# PCB-DISPARRAY4c.net
KiCad netlist of a schematic drawn in EAGLE
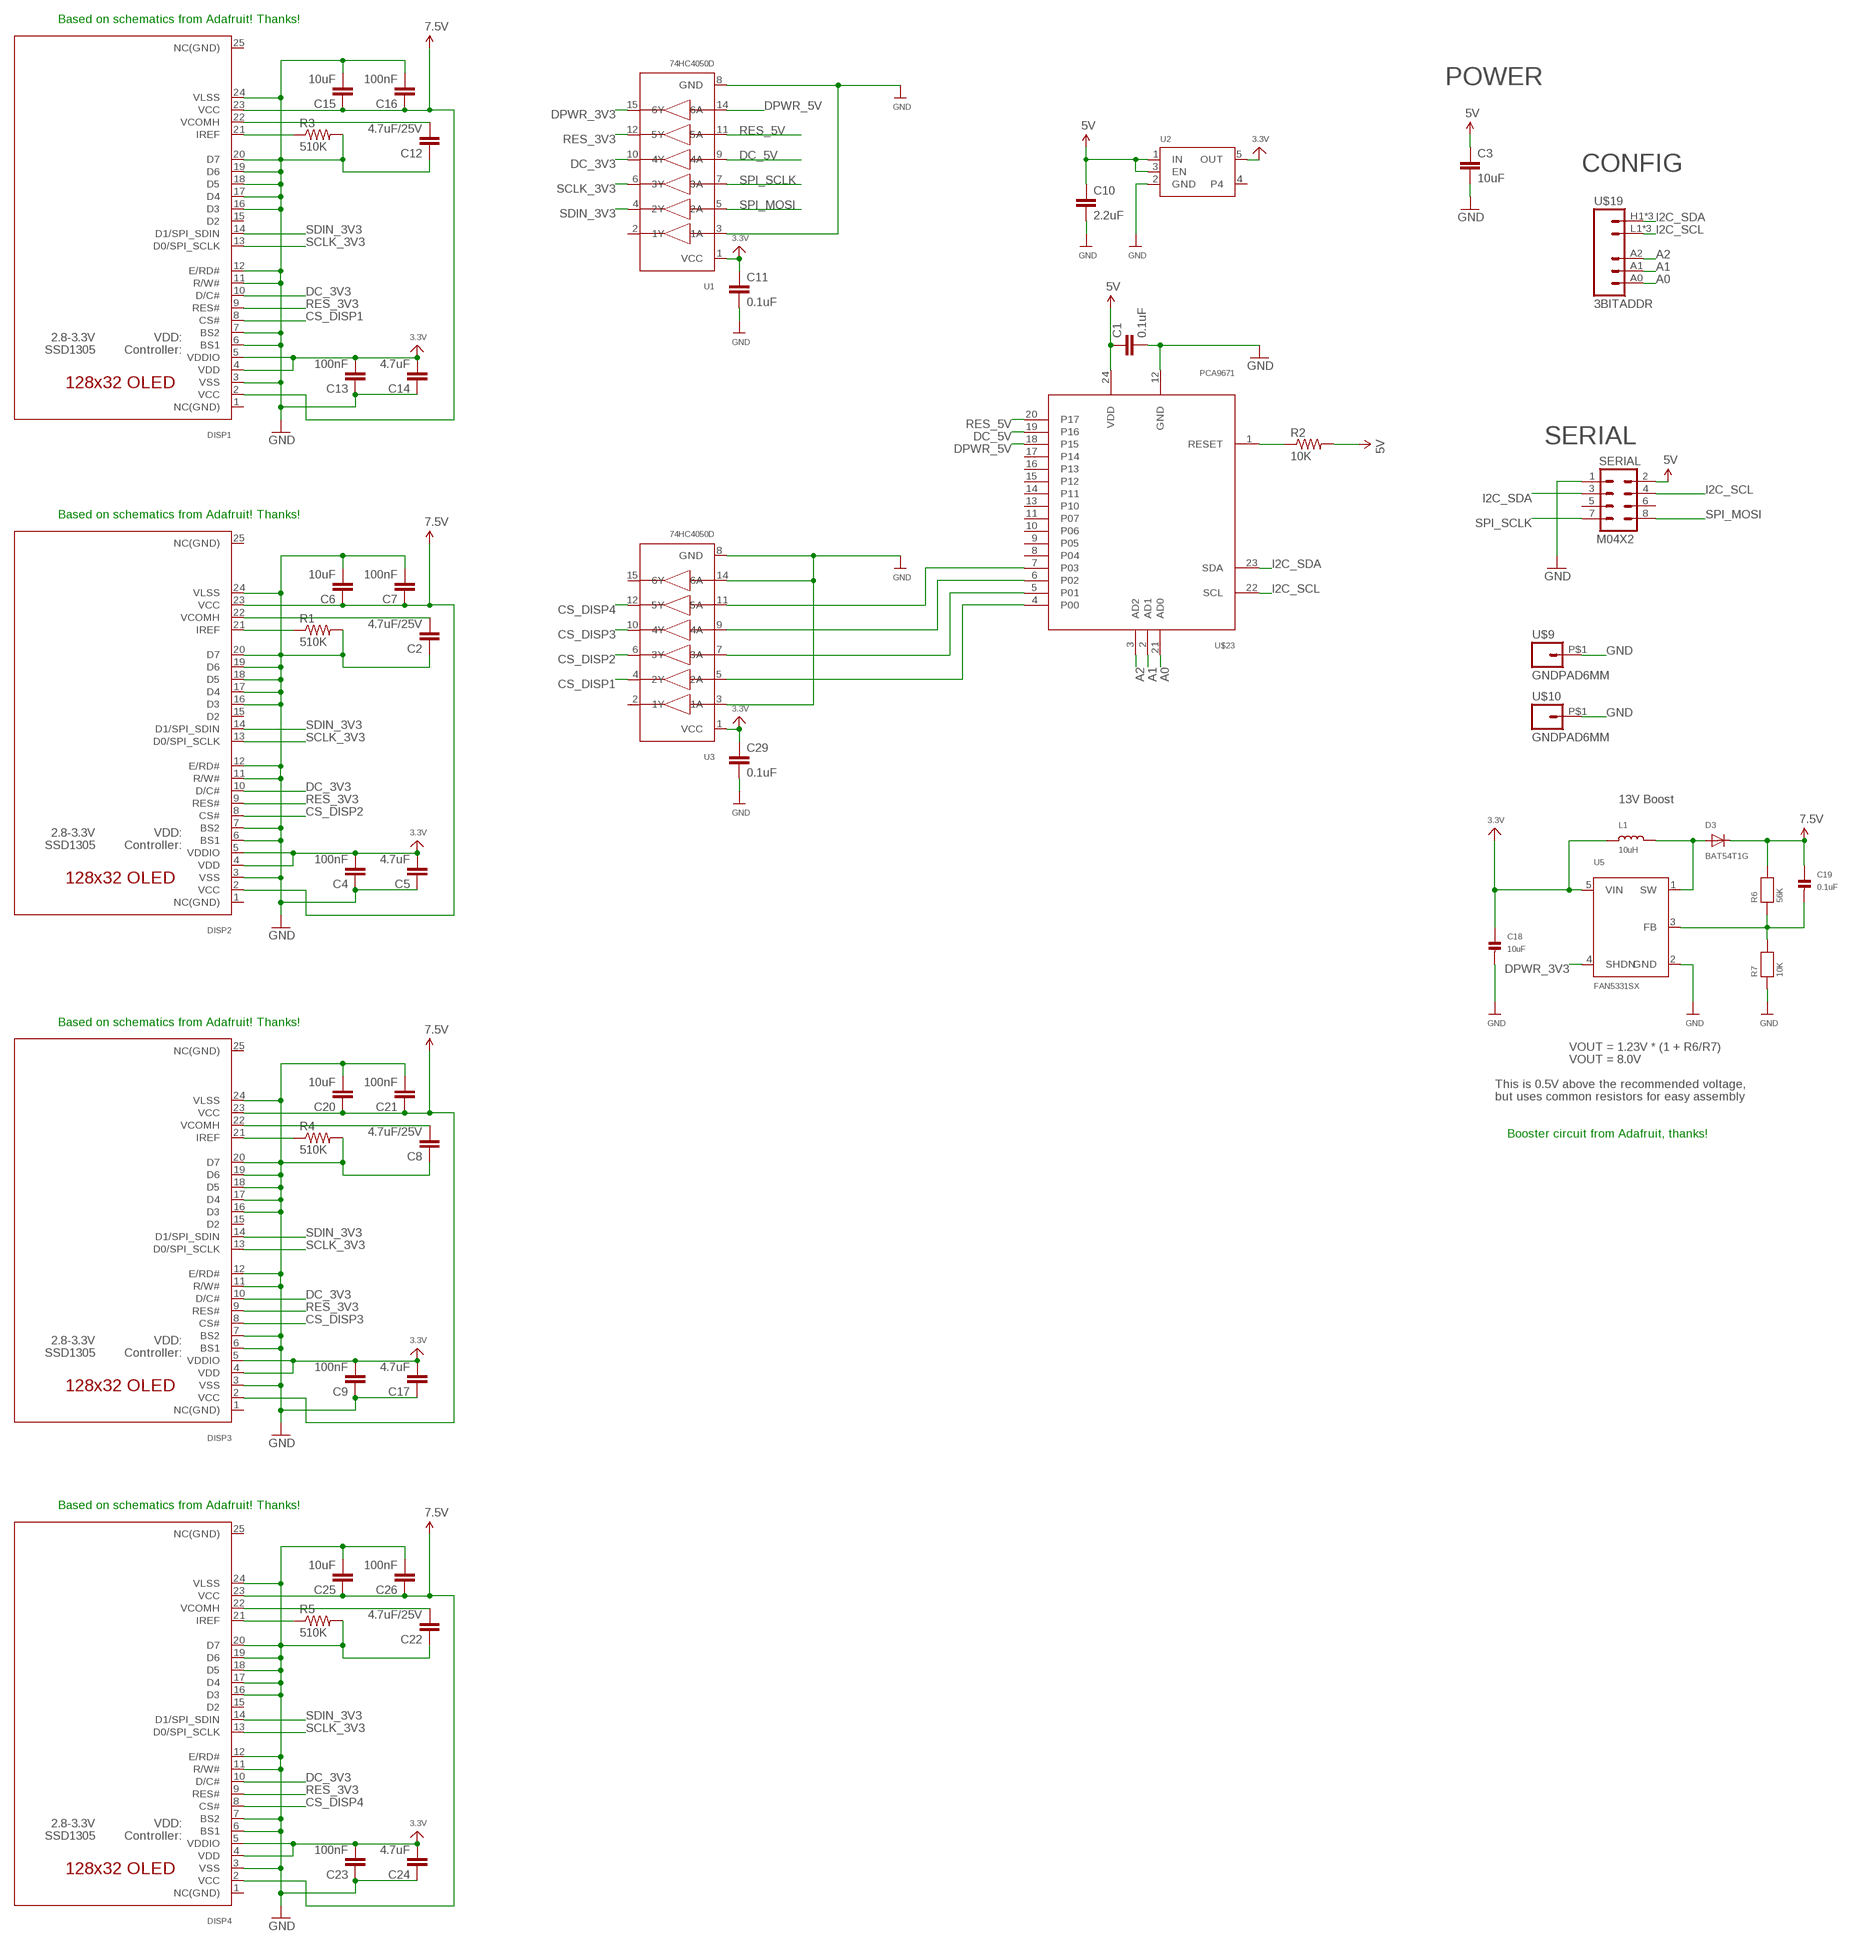
[diagram p0: schematic, sheet 1]

(export (version "E")
  (design (tool "Eeschema 10.0.6"))
  (components
    (comp (ref "C1")
      (value "0.1uF")
      (footprint "eagle-import:0603-CAP")
      (libsource (lib "eagle-import") (part "CAP0603-CAP"))
    )
    (comp (ref "C2")
      (value "4.7uF/25V")
      (footprint "eagle-import:0805")
      (libsource (lib "eagle-import") (part "CAP0805"))
    )
    (comp (ref "C3")
      (value "10uF")
      (footprint "eagle-import:0805")
      (libsource (lib "eagle-import") (part "CAP0805"))
    )
    (comp (ref "C4")
      (value "100nF")
      (footprint "eagle-import:0603-CAP")
      (libsource (lib "eagle-import") (part "CAP0603-CAP"))
    )
    (comp (ref "C5")
      (value "4.7uF")
      (footprint "eagle-import:0603-CAP")
      (libsource (lib "eagle-import") (part "CAP0603-CAP"))
    )
    (comp (ref "C6")
      (value "10uF")
      (footprint "eagle-import:0805")
      (libsource (lib "eagle-import") (part "CAP0805"))
    )
    (comp (ref "C7")
      (value "100nF")
      (footprint "eagle-import:0805")
      (libsource (lib "eagle-import") (part "CAP0805"))
    )
    (comp (ref "C8")
      (value "4.7uF/25V")
      (footprint "eagle-import:0805")
      (libsource (lib "eagle-import") (part "CAP0805"))
    )
    (comp (ref "C9")
      (value "100nF")
      (footprint "eagle-import:0603-CAP")
      (libsource (lib "eagle-import") (part "CAP0603-CAP"))
    )
    (comp (ref "C10")
      (value "2.2uF")
      (footprint "eagle-import:0603-CAP")
      (libsource (lib "eagle-import") (part "CAP0603-CAP"))
    )
    (comp (ref "C11")
      (value "0.1uF")
      (footprint "eagle-import:0603-CAP")
      (libsource (lib "eagle-import") (part "CAP0603-CAP"))
    )
    (comp (ref "C12")
      (value "4.7uF/25V")
      (footprint "eagle-import:0805")
      (libsource (lib "eagle-import") (part "CAP0805"))
    )
    (comp (ref "C13")
      (value "100nF")
      (footprint "eagle-import:0603-CAP")
      (libsource (lib "eagle-import") (part "CAP0603-CAP"))
    )
    (comp (ref "C14")
      (value "4.7uF")
      (footprint "eagle-import:0603-CAP")
      (libsource (lib "eagle-import") (part "CAP0603-CAP"))
    )
    (comp (ref "C15")
      (value "10uF")
      (footprint "eagle-import:0805")
      (libsource (lib "eagle-import") (part "CAP0805"))
    )
    (comp (ref "C16")
      (value "100nF")
      (footprint "eagle-import:0603-CAP")
      (libsource (lib "eagle-import") (part "CAP0603-CAP"))
    )
    (comp (ref "C17")
      (value "4.7uF")
      (footprint "eagle-import:0603-CAP")
      (libsource (lib "eagle-import") (part "CAP0603-CAP"))
    )
    (comp (ref "C18")
      (value "10uF")
      (footprint "eagle-import:0805")
      (libsource (lib "eagle-import") (part "CAP_CERAMIC0805"))
    )
    (comp (ref "C19")
      (value "0.1uF")
      (footprint "eagle-import:0603")
      (libsource (lib "eagle-import") (part "CAP_CERAMIC0603"))
    )
    (comp (ref "C20")
      (value "10uF")
      (footprint "eagle-import:0805")
      (libsource (lib "eagle-import") (part "CAP0805"))
    )
    (comp (ref "C21")
      (value "100nF")
      (footprint "eagle-import:0603-CAP")
      (libsource (lib "eagle-import") (part "CAP0603-CAP"))
    )
    (comp (ref "C22")
      (value "4.7uF/25V")
      (footprint "eagle-import:0805")
      (libsource (lib "eagle-import") (part "CAP0805"))
    )
    (comp (ref "C23")
      (value "100nF")
      (footprint "eagle-import:0603-CAP")
      (libsource (lib "eagle-import") (part "CAP0603-CAP"))
    )
    (comp (ref "C24")
      (value "4.7uF")
      (footprint "eagle-import:0603-CAP")
      (libsource (lib "eagle-import") (part "CAP0603-CAP"))
    )
    (comp (ref "C25")
      (value "10uF")
      (footprint "eagle-import:0805")
      (libsource (lib "eagle-import") (part "CAP0805"))
    )
    (comp (ref "C26")
      (value "100nF")
      (footprint "eagle-import:0603-CAP")
      (libsource (lib "eagle-import") (part "CAP0603-CAP"))
    )
    (comp (ref "C29")
      (value "0.1uF")
      (footprint "eagle-import:0603-CAP")
      (libsource (lib "eagle-import") (part "CAP0603-CAP"))
    )
    (comp (ref "D3")
      (value "BAT54T1G")
      (footprint "eagle-import:SOD-123")
      (libsource (lib "eagle-import") (part "DIODESOD-123"))
    )
    (comp (ref "DISP1")
      (value "ER-OLED0.91-2TOP")
      (footprint "eagle-import:ER_OLED0.91-2")
      (libsource (lib "eagle-import") (part "ER-OLED0.91-2TOP"))
    )
    (comp (ref "DISP2")
      (value "ER-OLED0.91-2TOP")
      (footprint "eagle-import:ER_OLED0.91-2")
      (libsource (lib "eagle-import") (part "ER-OLED0.91-2TOP"))
    )
    (comp (ref "DISP3")
      (value "ER-OLED0.91-2TOP")
      (footprint "eagle-import:ER_OLED0.91-2")
      (libsource (lib "eagle-import") (part "ER-OLED0.91-2TOP"))
    )
    (comp (ref "DISP4")
      (value "ER-OLED0.91-2TOP")
      (footprint "eagle-import:ER_OLED0.91-2")
      (libsource (lib "eagle-import") (part "ER-OLED0.91-2TOP"))
    )
    (comp (ref "L1")
      (value "10uH")
      (footprint "eagle-import:INDUCTOR_1007")
      (libsource (lib "eagle-import") (part "INDUCTOR"))
    )
    (comp (ref "R1")
      (value "510K")
      (footprint "eagle-import:0603-RES")
      (libsource (lib "eagle-import") (part "RESISTOR0603-RES"))
    )
    (comp (ref "R2")
      (value "10K")
      (footprint "eagle-import:0603-RES")
      (libsource (lib "eagle-import") (part "RESISTOR0603-RES"))
    )
    (comp (ref "R3")
      (value "510K")
      (footprint "eagle-import:0603-RES")
      (libsource (lib "eagle-import") (part "RESISTOR0603-RES"))
    )
    (comp (ref "R4")
      (value "510K")
      (footprint "eagle-import:0603-RES")
      (libsource (lib "eagle-import") (part "RESISTOR0603-RES"))
    )
    (comp (ref "R5")
      (value "510K")
      (footprint "eagle-import:0603-RES")
      (libsource (lib "eagle-import") (part "RESISTOR0603-RES"))
    )
    (comp (ref "R6")
      (value "56K")
      (footprint "eagle-import:0603")
      (libsource (lib "eagle-import") (part "RESISTOR0603"))
    )
    (comp (ref "R7")
      (value "10K")
      (footprint "eagle-import:0603")
      (libsource (lib "eagle-import") (part "RESISTOR0603"))
    )
    (comp (ref "SERIAL")
      (value "M04X2")
      (footprint "eagle-import:2X4")
      (libsource (lib "eagle-import") (part "M04X2"))
    )
    (comp (ref "U$9")
      (value "GNDPAD6MM")
      (footprint "eagle-import:3.2MMPAD6MM")
      (libsource (lib "eagle-import") (part "GNDPAD6MM"))
    )
    (comp (ref "U$10")
      (value "GNDPAD6MM")
      (footprint "eagle-import:3.2MMPAD6MM")
      (libsource (lib "eagle-import") (part "GNDPAD6MM"))
    )
    (comp (ref "U$19")
      (value "3BITADDR")
      (footprint "eagle-import:3BITADDR")
      (libsource (lib "eagle-import") (part "3BITADDR"))
    )
    (comp (ref "U$23")
      (value "PCA9671")
      (footprint "eagle-import:TSSOP24")
      (libsource (lib "eagle-import") (part "PCA9671"))
    )
    (comp (ref "U1")
      (value "74HC4050D")
      (footprint "eagle-import:TSSOP16")
      (libsource (lib "eagle-import") (part "74HC4050DTSSOP16"))
    )
    (comp (ref "U2")
      (value "VREG_SOT23-5")
      (footprint "eagle-import:SOT23-5")
      (libsource (lib "eagle-import") (part "VREG_SOT23-5"))
    )
    (comp (ref "U3")
      (value "74HC4050D")
      (footprint "eagle-import:TSSOP16")
      (libsource (lib "eagle-import") (part "74HC4050DTSSOP16"))
    )
    (comp (ref "U5")
      (value "FAN5331SX")
      (footprint "eagle-import:SOT23-5")
      (libsource (lib "eagle-import") (part "FAN5331"))
    )
  )
  (nets
    (net (code "1") (name "3.3V") (class "Default")
      (node (ref "C11") (pin "1") (pinfunction "1_1") (pintype "passive"))
      (node (ref "C13") (pin "2") (pinfunction "2_2") (pintype "passive"))
      (node (ref "C14") (pin "2") (pinfunction "2_2") (pintype "passive"))
      (node (ref "C17") (pin "2") (pinfunction "2_2") (pintype "passive"))
      (node (ref "C18") (pin "1") (pinfunction "P$1_1") (pintype "passive"))
      (node (ref "C23") (pin "2") (pinfunction "2_2") (pintype "passive"))
      (node (ref "C24") (pin "2") (pinfunction "2_2") (pintype "passive"))
      (node (ref "C29") (pin "1") (pinfunction "1_1") (pintype "passive"))
      (node (ref "C4") (pin "2") (pinfunction "2_2") (pintype "passive"))
      (node (ref "C5") (pin "2") (pinfunction "2_2") (pintype "passive"))
      (node (ref "C9") (pin "2") (pinfunction "2_2") (pintype "passive"))
      (node (ref "DISP1") (pin "4") (pinfunction "VDD_4") (pintype "power_in"))
      (node (ref "DISP1") (pin "5") (pinfunction "VDDIO_5") (pintype "power_in"))
      (node (ref "DISP2") (pin "4") (pinfunction "VDD_4") (pintype "power_in"))
      (node (ref "DISP2") (pin "5") (pinfunction "VDDIO_5") (pintype "power_in"))
      (node (ref "DISP3") (pin "4") (pinfunction "VDD_4") (pintype "power_in"))
      (node (ref "DISP3") (pin "5") (pinfunction "VDDIO_5") (pintype "power_in"))
      (node (ref "DISP4") (pin "4") (pinfunction "VDD_4") (pintype "power_in"))
      (node (ref "DISP4") (pin "5") (pinfunction "VDDIO_5") (pintype "power_in"))
      (node (ref "L1") (pin "P$1") (pinfunction "1_P$1") (pintype "passive"))
      (node (ref "U1") (pin "1") (pinfunction "VCC_1") (pintype "bidirectional"))
      (node (ref "U2") (pin "5") (pinfunction "OUT_5") (pintype "bidirectional"))
      (node (ref "U3") (pin "1") (pinfunction "VCC_1") (pintype "bidirectional"))
      (node (ref "U5") (pin "5") (pinfunction "VIN_5") (pintype "bidirectional"))
    )
    (net (code "2") (name "5V") (class "Default")
      (node (ref "C1") (pin "1") (pinfunction "1_1") (pintype "passive"))
      (node (ref "C10") (pin "1") (pinfunction "1_1") (pintype "passive"))
      (node (ref "C3") (pin "1") (pinfunction "1_1") (pintype "passive"))
      (node (ref "R2") (pin "2") (pinfunction "2_2") (pintype "passive"))
      (node (ref "SERIAL") (pin "2") (pinfunction "2_2") (pintype "passive"))
      (node (ref "U$23") (pin "24") (pinfunction "VDD_24") (pintype "power_in"))
      (node (ref "U2") (pin "1") (pinfunction "IN_1") (pintype "bidirectional"))
      (node (ref "U2") (pin "3") (pinfunction "EN_3") (pintype "bidirectional"))
    )
    (net (code "3") (name "7.5V") (class "Default")
      (node (ref "C15") (pin "1") (pinfunction "1_1") (pintype "passive"))
      (node (ref "C16") (pin "1") (pinfunction "1_1") (pintype "passive"))
      (node (ref "C19") (pin "1") (pinfunction "P$1_1") (pintype "passive"))
      (node (ref "C20") (pin "1") (pinfunction "1_1") (pintype "passive"))
      (node (ref "C21") (pin "1") (pinfunction "1_1") (pintype "passive"))
      (node (ref "C25") (pin "1") (pinfunction "1_1") (pintype "passive"))
      (node (ref "C26") (pin "1") (pinfunction "1_1") (pintype "passive"))
      (node (ref "C6") (pin "1") (pinfunction "1_1") (pintype "passive"))
      (node (ref "C7") (pin "1") (pinfunction "1_1") (pintype "passive"))
      (node (ref "D3") (pin "C") (pinfunction "C_C") (pintype "passive"))
      (node (ref "DISP1") (pin "2") (pinfunction "VCC_2") (pintype "power_in"))
      (node (ref "DISP1") (pin "23") (pinfunction "VCC_23") (pintype "power_in"))
      (node (ref "DISP2") (pin "2") (pinfunction "VCC_2") (pintype "power_in"))
      (node (ref "DISP2") (pin "23") (pinfunction "VCC_23") (pintype "power_in"))
      (node (ref "DISP3") (pin "2") (pinfunction "VCC_2") (pintype "power_in"))
      (node (ref "DISP3") (pin "23") (pinfunction "VCC_23") (pintype "power_in"))
      (node (ref "DISP4") (pin "2") (pinfunction "VCC_2") (pintype "power_in"))
      (node (ref "DISP4") (pin "23") (pinfunction "VCC_23") (pintype "power_in"))
      (node (ref "R6") (pin "2") (pinfunction "2_2") (pintype "passive"))
    )
    (net (code "4") (name "A0") (class "Default")
      (node (ref "U$19") (pin "A0") (pinfunction "A0_A0") (pintype "passive"))
      (node (ref "U$23") (pin "21") (pinfunction "AD0_21") (pintype "input"))
    )
    (net (code "5") (name "A1") (class "Default")
      (node (ref "U$19") (pin "A1") (pinfunction "A1_A1") (pintype "passive"))
      (node (ref "U$23") (pin "2") (pinfunction "AD1_2") (pintype "input"))
    )
    (net (code "6") (name "A2") (class "Default")
      (node (ref "U$19") (pin "A2") (pinfunction "A2_A2") (pintype "passive"))
      (node (ref "U$23") (pin "3") (pinfunction "AD2_3") (pintype "input"))
    )
    (net (code "7") (name "CS_DISP1") (class "Default")
      (node (ref "DISP1") (pin "8") (pinfunction "CS#_8") (pintype "input"))
      (node (ref "U3") (pin "4") (pinfunction "2Y_4") (pintype "bidirectional"))
    )
    (net (code "8") (name "CS_DISP2") (class "Default")
      (node (ref "DISP2") (pin "8") (pinfunction "CS#_8") (pintype "input"))
      (node (ref "U3") (pin "6") (pinfunction "3Y_6") (pintype "bidirectional"))
    )
    (net (code "9") (name "CS_DISP3") (class "Default")
      (node (ref "DISP3") (pin "8") (pinfunction "CS#_8") (pintype "input"))
      (node (ref "U3") (pin "10") (pinfunction "4Y_10") (pintype "bidirectional"))
    )
    (net (code "10") (name "CS_DISP4") (class "Default")
      (node (ref "DISP4") (pin "8") (pinfunction "CS#_8") (pintype "input"))
      (node (ref "U3") (pin "12") (pinfunction "5Y_12") (pintype "bidirectional"))
    )
    (net (code "11") (name "DC_3V3") (class "Default")
      (node (ref "DISP1") (pin "10") (pinfunction "D/C#_10") (pintype "input"))
      (node (ref "DISP2") (pin "10") (pinfunction "D/C#_10") (pintype "input"))
      (node (ref "DISP3") (pin "10") (pinfunction "D/C#_10") (pintype "input"))
      (node (ref "DISP4") (pin "10") (pinfunction "D/C#_10") (pintype "input"))
      (node (ref "U1") (pin "10") (pinfunction "4Y_10") (pintype "bidirectional"))
    )
    (net (code "12") (name "DC_5V") (class "Default")
      (node (ref "U$23") (pin "19") (pinfunction "P16_19") (pintype "output"))
      (node (ref "U1") (pin "9") (pinfunction "4A_9") (pintype "bidirectional"))
    )
    (net (code "13") (name "DPWR_3V3") (class "Default")
      (node (ref "U1") (pin "15") (pinfunction "6Y_15") (pintype "bidirectional"))
      (node (ref "U5") (pin "4") (pinfunction "SHDN_4") (pintype "bidirectional"))
    )
    (net (code "14") (name "DPWR_5V") (class "Default")
      (node (ref "U$23") (pin "18") (pinfunction "P15_18") (pintype "output"))
      (node (ref "U1") (pin "14") (pinfunction "6A_14") (pintype "bidirectional"))
    )
    (net (code "15") (name "GND") (class "Default")
      (node (ref "C1") (pin "2") (pinfunction "2_2") (pintype "passive"))
      (node (ref "C10") (pin "2") (pinfunction "2_2") (pintype "passive"))
      (node (ref "C11") (pin "2") (pinfunction "2_2") (pintype "passive"))
      (node (ref "C12") (pin "1") (pinfunction "1_1") (pintype "passive"))
      (node (ref "C13") (pin "1") (pinfunction "1_1") (pintype "passive"))
      (node (ref "C14") (pin "1") (pinfunction "1_1") (pintype "passive"))
      (node (ref "C15") (pin "2") (pinfunction "2_2") (pintype "passive"))
      (node (ref "C16") (pin "2") (pinfunction "2_2") (pintype "passive"))
      (node (ref "C17") (pin "1") (pinfunction "1_1") (pintype "passive"))
      (node (ref "C18") (pin "2") (pinfunction "P$2_2") (pintype "passive"))
      (node (ref "C2") (pin "1") (pinfunction "1_1") (pintype "passive"))
      (node (ref "C20") (pin "2") (pinfunction "2_2") (pintype "passive"))
      (node (ref "C21") (pin "2") (pinfunction "2_2") (pintype "passive"))
      (node (ref "C22") (pin "1") (pinfunction "1_1") (pintype "passive"))
      (node (ref "C23") (pin "1") (pinfunction "1_1") (pintype "passive"))
      (node (ref "C24") (pin "1") (pinfunction "1_1") (pintype "passive"))
      (node (ref "C25") (pin "2") (pinfunction "2_2") (pintype "passive"))
      (node (ref "C26") (pin "2") (pinfunction "2_2") (pintype "passive"))
      (node (ref "C29") (pin "2") (pinfunction "2_2") (pintype "passive"))
      (node (ref "C3") (pin "2") (pinfunction "2_2") (pintype "passive"))
      (node (ref "C4") (pin "1") (pinfunction "1_1") (pintype "passive"))
      (node (ref "C5") (pin "1") (pinfunction "1_1") (pintype "passive"))
      (node (ref "C6") (pin "2") (pinfunction "2_2") (pintype "passive"))
      (node (ref "C7") (pin "2") (pinfunction "2_2") (pintype "passive"))
      (node (ref "C8") (pin "1") (pinfunction "1_1") (pintype "passive"))
      (node (ref "C9") (pin "1") (pinfunction "1_1") (pintype "passive"))
      (node (ref "DISP1") (pin "11") (pinfunction "R/W#_11") (pintype "input"))
      (node (ref "DISP1") (pin "12") (pinfunction "E/RD#_12") (pintype "input"))
      (node (ref "DISP1") (pin "16") (pinfunction "D3_16") (pintype "bidirectional"))
      (node (ref "DISP1") (pin "17") (pinfunction "D4_17") (pintype "bidirectional"))
      (node (ref "DISP1") (pin "18") (pinfunction "D5_18") (pintype "bidirectional"))
      (node (ref "DISP1") (pin "19") (pinfunction "D6_19") (pintype "bidirectional"))
      (node (ref "DISP1") (pin "20") (pinfunction "D7_20") (pintype "bidirectional"))
      (node (ref "DISP1") (pin "24") (pinfunction "VLSS_24") (pintype "power_in"))
      (node (ref "DISP1") (pin "3") (pinfunction "VSS_3") (pintype "power_in"))
      (node (ref "DISP1") (pin "6") (pinfunction "BS1_6") (pintype "input"))
      (node (ref "DISP1") (pin "7") (pinfunction "BS2_7") (pintype "input"))
      (node (ref "DISP2") (pin "11") (pinfunction "R/W#_11") (pintype "input"))
      (node (ref "DISP2") (pin "12") (pinfunction "E/RD#_12") (pintype "input"))
      (node (ref "DISP2") (pin "16") (pinfunction "D3_16") (pintype "bidirectional"))
      (node (ref "DISP2") (pin "17") (pinfunction "D4_17") (pintype "bidirectional"))
      (node (ref "DISP2") (pin "18") (pinfunction "D5_18") (pintype "bidirectional"))
      (node (ref "DISP2") (pin "19") (pinfunction "D6_19") (pintype "bidirectional"))
      (node (ref "DISP2") (pin "20") (pinfunction "D7_20") (pintype "bidirectional"))
      (node (ref "DISP2") (pin "24") (pinfunction "VLSS_24") (pintype "power_in"))
      (node (ref "DISP2") (pin "3") (pinfunction "VSS_3") (pintype "power_in"))
      (node (ref "DISP2") (pin "6") (pinfunction "BS1_6") (pintype "input"))
      (node (ref "DISP2") (pin "7") (pinfunction "BS2_7") (pintype "input"))
      (node (ref "DISP3") (pin "11") (pinfunction "R/W#_11") (pintype "input"))
      (node (ref "DISP3") (pin "12") (pinfunction "E/RD#_12") (pintype "input"))
      (node (ref "DISP3") (pin "16") (pinfunction "D3_16") (pintype "bidirectional"))
      (node (ref "DISP3") (pin "17") (pinfunction "D4_17") (pintype "bidirectional"))
      (node (ref "DISP3") (pin "18") (pinfunction "D5_18") (pintype "bidirectional"))
      (node (ref "DISP3") (pin "19") (pinfunction "D6_19") (pintype "bidirectional"))
      (node (ref "DISP3") (pin "20") (pinfunction "D7_20") (pintype "bidirectional"))
      (node (ref "DISP3") (pin "24") (pinfunction "VLSS_24") (pintype "power_in"))
      (node (ref "DISP3") (pin "3") (pinfunction "VSS_3") (pintype "power_in"))
      (node (ref "DISP3") (pin "6") (pinfunction "BS1_6") (pintype "input"))
      (node (ref "DISP3") (pin "7") (pinfunction "BS2_7") (pintype "input"))
      (node (ref "DISP4") (pin "11") (pinfunction "R/W#_11") (pintype "input"))
      (node (ref "DISP4") (pin "12") (pinfunction "E/RD#_12") (pintype "input"))
      (node (ref "DISP4") (pin "16") (pinfunction "D3_16") (pintype "bidirectional"))
      (node (ref "DISP4") (pin "17") (pinfunction "D4_17") (pintype "bidirectional"))
      (node (ref "DISP4") (pin "18") (pinfunction "D5_18") (pintype "bidirectional"))
      (node (ref "DISP4") (pin "19") (pinfunction "D6_19") (pintype "bidirectional"))
      (node (ref "DISP4") (pin "20") (pinfunction "D7_20") (pintype "bidirectional"))
      (node (ref "DISP4") (pin "24") (pinfunction "VLSS_24") (pintype "power_in"))
      (node (ref "DISP4") (pin "3") (pinfunction "VSS_3") (pintype "power_in"))
      (node (ref "DISP4") (pin "6") (pinfunction "BS1_6") (pintype "input"))
      (node (ref "DISP4") (pin "7") (pinfunction "BS2_7") (pintype "input"))
      (node (ref "R1") (pin "2") (pinfunction "2_2") (pintype "passive"))
      (node (ref "R3") (pin "2") (pinfunction "2_2") (pintype "passive"))
      (node (ref "R4") (pin "2") (pinfunction "2_2") (pintype "passive"))
      (node (ref "R5") (pin "2") (pinfunction "2_2") (pintype "passive"))
      (node (ref "R7") (pin "1") (pinfunction "1_1") (pintype "passive"))
      (node (ref "SERIAL") (pin "1") (pinfunction "1_1") (pintype "passive"))
      (node (ref "U$10") (pin "P$1") (pinfunction "1_P$1") (pintype "passive"))
      (node (ref "U$23") (pin "12") (pinfunction "GND_12") (pintype "power_in"))
      (node (ref "U$9") (pin "P$1") (pinfunction "1_P$1") (pintype "passive"))
      (node (ref "U1") (pin "3") (pinfunction "1A_3") (pintype "bidirectional"))
      (node (ref "U1") (pin "8") (pinfunction "GND_8") (pintype "bidirectional"))
      (node (ref "U2") (pin "2") (pinfunction "GND_2") (pintype "bidirectional"))
      (node (ref "U3") (pin "14") (pinfunction "6A_14") (pintype "bidirectional"))
      (node (ref "U3") (pin "3") (pinfunction "1A_3") (pintype "bidirectional"))
      (node (ref "U3") (pin "8") (pinfunction "GND_8") (pintype "bidirectional"))
      (node (ref "U5") (pin "2") (pinfunction "GND_2") (pintype "bidirectional"))
    )
    (net (code "16") (name "I2C_SCL") (class "Default")
      (node (ref "SERIAL") (pin "4") (pinfunction "4_4") (pintype "passive"))
      (node (ref "U$19") (pin "L1") (pinfunction "GND_L1") (pintype "passive"))
      (node (ref "U$19") (pin "L2") (pinfunction "GND_L2") (pintype "passive"))
      (node (ref "U$19") (pin "L3") (pinfunction "GND_L3") (pintype "passive"))
      (node (ref "U$23") (pin "22") (pinfunction "SCL_22") (pintype "input"))
    )
    (net (code "17") (name "I2C_SDA") (class "Default")
      (node (ref "SERIAL") (pin "3") (pinfunction "3_3") (pintype "passive"))
      (node (ref "U$19") (pin "H1") (pinfunction "VCC_H1") (pintype "passive"))
      (node (ref "U$19") (pin "H2") (pinfunction "VCC_H2") (pintype "passive"))
      (node (ref "U$19") (pin "H3") (pinfunction "VCC_H3") (pintype "passive"))
      (node (ref "U$23") (pin "23") (pinfunction "SDA_23") (pintype "input"))
    )
    (net (code "18") (name "Net-(C19-P$2)") (class "Default")
      (node (ref "C19") (pin "2") (pinfunction "P$2_2") (pintype "passive"))
      (node (ref "R6") (pin "1") (pinfunction "1_1") (pintype "passive"))
      (node (ref "R7") (pin "2") (pinfunction "2_2") (pintype "passive"))
      (node (ref "U5") (pin "3") (pinfunction "FB_3") (pintype "bidirectional"))
    )
    (net (code "19") (name "Net-(DISP1-IREF)") (class "Default")
      (node (ref "DISP1") (pin "21") (pinfunction "IREF_21") (pintype "input"))
      (node (ref "R3") (pin "1") (pinfunction "1_1") (pintype "passive"))
    )
    (net (code "20") (name "Net-(DISP1-VCOMH)") (class "Default")
      (node (ref "C12") (pin "2") (pinfunction "2_2") (pintype "passive"))
      (node (ref "DISP1") (pin "22") (pinfunction "VCOMH_22") (pintype "output"))
    )
    (net (code "21") (name "Net-(DISP2-IREF)") (class "Default")
      (node (ref "DISP2") (pin "21") (pinfunction "IREF_21") (pintype "input"))
      (node (ref "R1") (pin "1") (pinfunction "1_1") (pintype "passive"))
    )
    (net (code "22") (name "Net-(DISP2-VCOMH)") (class "Default")
      (node (ref "C2") (pin "2") (pinfunction "2_2") (pintype "passive"))
      (node (ref "DISP2") (pin "22") (pinfunction "VCOMH_22") (pintype "output"))
    )
    (net (code "23") (name "Net-(DISP3-IREF)") (class "Default")
      (node (ref "DISP3") (pin "21") (pinfunction "IREF_21") (pintype "input"))
      (node (ref "R4") (pin "1") (pinfunction "1_1") (pintype "passive"))
    )
    (net (code "24") (name "Net-(DISP3-VCOMH)") (class "Default")
      (node (ref "C8") (pin "2") (pinfunction "2_2") (pintype "passive"))
      (node (ref "DISP3") (pin "22") (pinfunction "VCOMH_22") (pintype "output"))
    )
    (net (code "25") (name "Net-(DISP4-IREF)") (class "Default")
      (node (ref "DISP4") (pin "21") (pinfunction "IREF_21") (pintype "input"))
      (node (ref "R5") (pin "1") (pinfunction "1_1") (pintype "passive"))
    )
    (net (code "26") (name "Net-(DISP4-VCOMH)") (class "Default")
      (node (ref "C22") (pin "2") (pinfunction "2_2") (pintype "passive"))
      (node (ref "DISP4") (pin "22") (pinfunction "VCOMH_22") (pintype "output"))
    )
    (net (code "27") (name "Net-(L1-2)") (class "Default")
      (node (ref "D3") (pin "A") (pinfunction "A_A") (pintype "passive"))
      (node (ref "L1") (pin "P$2") (pinfunction "2_P$2") (pintype "passive"))
      (node (ref "U5") (pin "1") (pinfunction "SW_1") (pintype "bidirectional"))
    )
    (net (code "28") (name "Net-(U$23-P00)") (class "Default")
      (node (ref "U$23") (pin "4") (pinfunction "P00_4") (pintype "output"))
      (node (ref "U3") (pin "5") (pinfunction "2A_5") (pintype "bidirectional"))
    )
    (net (code "29") (name "Net-(U$23-P01)") (class "Default")
      (node (ref "U$23") (pin "5") (pinfunction "P01_5") (pintype "output"))
      (node (ref "U3") (pin "7") (pinfunction "3A_7") (pintype "bidirectional"))
    )
    (net (code "30") (name "Net-(U$23-P02)") (class "Default")
      (node (ref "U$23") (pin "6") (pinfunction "P02_6") (pintype "output"))
      (node (ref "U3") (pin "9") (pinfunction "4A_9") (pintype "bidirectional"))
    )
    (net (code "31") (name "Net-(U$23-P03)") (class "Default")
      (node (ref "U$23") (pin "7") (pinfunction "P03_7") (pintype "output"))
      (node (ref "U3") (pin "11") (pinfunction "5A_11") (pintype "bidirectional"))
    )
    (net (code "32") (name "Net-(U$23-RESET)") (class "Default")
      (node (ref "R2") (pin "1") (pinfunction "1_1") (pintype "passive"))
      (node (ref "U$23") (pin "1") (pinfunction "RESET_1") (pintype "input"))
    )
    (net (code "33") (name "RES_3V3") (class "Default")
      (node (ref "DISP1") (pin "9") (pinfunction "RES#_9") (pintype "input"))
      (node (ref "DISP2") (pin "9") (pinfunction "RES#_9") (pintype "input"))
      (node (ref "DISP3") (pin "9") (pinfunction "RES#_9") (pintype "input"))
      (node (ref "DISP4") (pin "9") (pinfunction "RES#_9") (pintype "input"))
      (node (ref "U1") (pin "12") (pinfunction "5Y_12") (pintype "bidirectional"))
    )
    (net (code "34") (name "RES_5V") (class "Default")
      (node (ref "U$23") (pin "20") (pinfunction "P17_20") (pintype "output"))
      (node (ref "U1") (pin "11") (pinfunction "5A_11") (pintype "bidirectional"))
    )
    (net (code "35") (name "SCLK_3V3") (class "Default")
      (node (ref "DISP1") (pin "13") (pinfunction "D0/SPI_SCLK_13") (pintype "bidirectional"))
      (node (ref "DISP2") (pin "13") (pinfunction "D0/SPI_SCLK_13") (pintype "bidirectional"))
      (node (ref "DISP3") (pin "13") (pinfunction "D0/SPI_SCLK_13") (pintype "bidirectional"))
      (node (ref "DISP4") (pin "13") (pinfunction "D0/SPI_SCLK_13") (pintype "bidirectional"))
      (node (ref "U1") (pin "6") (pinfunction "3Y_6") (pintype "bidirectional"))
    )
    (net (code "36") (name "SDIN_3V3") (class "Default")
      (node (ref "DISP1") (pin "14") (pinfunction "D1/SPI_SDIN_14") (pintype "bidirectional"))
      (node (ref "DISP2") (pin "14") (pinfunction "D1/SPI_SDIN_14") (pintype "bidirectional"))
      (node (ref "DISP3") (pin "14") (pinfunction "D1/SPI_SDIN_14") (pintype "bidirectional"))
      (node (ref "DISP4") (pin "14") (pinfunction "D1/SPI_SDIN_14") (pintype "bidirectional"))
      (node (ref "U1") (pin "4") (pinfunction "2Y_4") (pintype "bidirectional"))
    )
    (net (code "37") (name "SPI_MOSI") (class "Default")
      (node (ref "SERIAL") (pin "8") (pinfunction "8_8") (pintype "passive"))
      (node (ref "U1") (pin "5") (pinfunction "2A_5") (pintype "bidirectional"))
    )
    (net (code "38") (name "SPI_SCLK") (class "Default")
      (node (ref "SERIAL") (pin "7") (pinfunction "7_7") (pintype "passive"))
      (node (ref "U1") (pin "7") (pinfunction "3A_7") (pintype "bidirectional"))
    )
    (net (code "39") (name "unconnected-(DISP1-D2-Pad15)") (class "Default")
      (node (ref "DISP1") (pin "15") (pinfunction "D2_15") (pintype "bidirectional"))
    )
    (net (code "40") (name "unconnected-(DISP1-NC(GND)-Pad1)") (class "Default")
      (node (ref "DISP1") (pin "1") (pinfunction "NC(GND)_1") (pintype "input"))
    )
    (net (code "41") (name "unconnected-(DISP1-NC(GND)-Pad25)") (class "Default")
      (node (ref "DISP1") (pin "25") (pinfunction "NC(GND)_25") (pintype "input"))
    )
    (net (code "42") (name "unconnected-(DISP2-D2-Pad15)") (class "Default")
      (node (ref "DISP2") (pin "15") (pinfunction "D2_15") (pintype "bidirectional"))
    )
    (net (code "43") (name "unconnected-(DISP2-NC(GND)-Pad1)") (class "Default")
      (node (ref "DISP2") (pin "1") (pinfunction "NC(GND)_1") (pintype "input"))
    )
    (net (code "44") (name "unconnected-(DISP2-NC(GND)-Pad25)") (class "Default")
      (node (ref "DISP2") (pin "25") (pinfunction "NC(GND)_25") (pintype "input"))
    )
    (net (code "45") (name "unconnected-(DISP3-D2-Pad15)") (class "Default")
      (node (ref "DISP3") (pin "15") (pinfunction "D2_15") (pintype "bidirectional"))
    )
    (net (code "46") (name "unconnected-(DISP3-NC(GND)-Pad1)") (class "Default")
      (node (ref "DISP3") (pin "1") (pinfunction "NC(GND)_1") (pintype "input"))
    )
    (net (code "47") (name "unconnected-(DISP3-NC(GND)-Pad25)") (class "Default")
      (node (ref "DISP3") (pin "25") (pinfunction "NC(GND)_25") (pintype "input"))
    )
    (net (code "48") (name "unconnected-(DISP4-D2-Pad15)") (class "Default")
      (node (ref "DISP4") (pin "15") (pinfunction "D2_15") (pintype "bidirectional"))
    )
    (net (code "49") (name "unconnected-(DISP4-NC(GND)-Pad1)") (class "Default")
      (node (ref "DISP4") (pin "1") (pinfunction "NC(GND)_1") (pintype "input"))
    )
    (net (code "50") (name "unconnected-(DISP4-NC(GND)-Pad25)") (class "Default")
      (node (ref "DISP4") (pin "25") (pinfunction "NC(GND)_25") (pintype "input"))
    )
    (net (code "51") (name "unconnected-(SERIAL-Pad5)") (class "Default")
      (node (ref "SERIAL") (pin "5") (pinfunction "5_5") (pintype "passive"))
    )
    (net (code "52") (name "unconnected-(SERIAL-Pad6)") (class "Default")
      (node (ref "SERIAL") (pin "6") (pinfunction "6_6") (pintype "passive"))
    )
    (net (code "53") (name "unconnected-(U$23-P04-Pad8)") (class "Default")
      (node (ref "U$23") (pin "8") (pinfunction "P04_8") (pintype "output"))
    )
    (net (code "54") (name "unconnected-(U$23-P05-Pad9)") (class "Default")
      (node (ref "U$23") (pin "9") (pinfunction "P05_9") (pintype "output"))
    )
    (net (code "55") (name "unconnected-(U$23-P06-Pad10)") (class "Default")
      (node (ref "U$23") (pin "10") (pinfunction "P06_10") (pintype "output"))
    )
    (net (code "56") (name "unconnected-(U$23-P07-Pad11)") (class "Default")
      (node (ref "U$23") (pin "11") (pinfunction "P07_11") (pintype "output"))
    )
    (net (code "57") (name "unconnected-(U$23-P10-Pad13)") (class "Default")
      (node (ref "U$23") (pin "13") (pinfunction "P10_13") (pintype "output"))
    )
    (net (code "58") (name "unconnected-(U$23-P11-Pad14)") (class "Default")
      (node (ref "U$23") (pin "14") (pinfunction "P11_14") (pintype "output"))
    )
    (net (code "59") (name "unconnected-(U$23-P12-Pad15)") (class "Default")
      (node (ref "U$23") (pin "15") (pinfunction "P12_15") (pintype "output"))
    )
    (net (code "60") (name "unconnected-(U$23-P13-Pad16)") (class "Default")
      (node (ref "U$23") (pin "16") (pinfunction "P13_16") (pintype "output"))
    )
    (net (code "61") (name "unconnected-(U$23-P14-Pad17)") (class "Default")
      (node (ref "U$23") (pin "17") (pinfunction "P14_17") (pintype "output"))
    )
    (net (code "62") (name "unconnected-(U1-1Y-Pad2)") (class "Default")
      (node (ref "U1") (pin "2") (pinfunction "1Y_2") (pintype "bidirectional"))
    )
    (net (code "63") (name "unconnected-(U2-P4-Pad4)") (class "Default")
      (node (ref "U2") (pin "4") (pinfunction "P4_4") (pintype "bidirectional"))
    )
    (net (code "64") (name "unconnected-(U3-1Y-Pad2)") (class "Default")
      (node (ref "U3") (pin "2") (pinfunction "1Y_2") (pintype "bidirectional"))
    )
    (net (code "65") (name "unconnected-(U3-6Y-Pad15)") (class "Default")
      (node (ref "U3") (pin "15") (pinfunction "6Y_15") (pintype "bidirectional"))
    )
  )
)
